# Procesador_Principal.net
KiCad netlist of a schematic drawn in Altium Designer
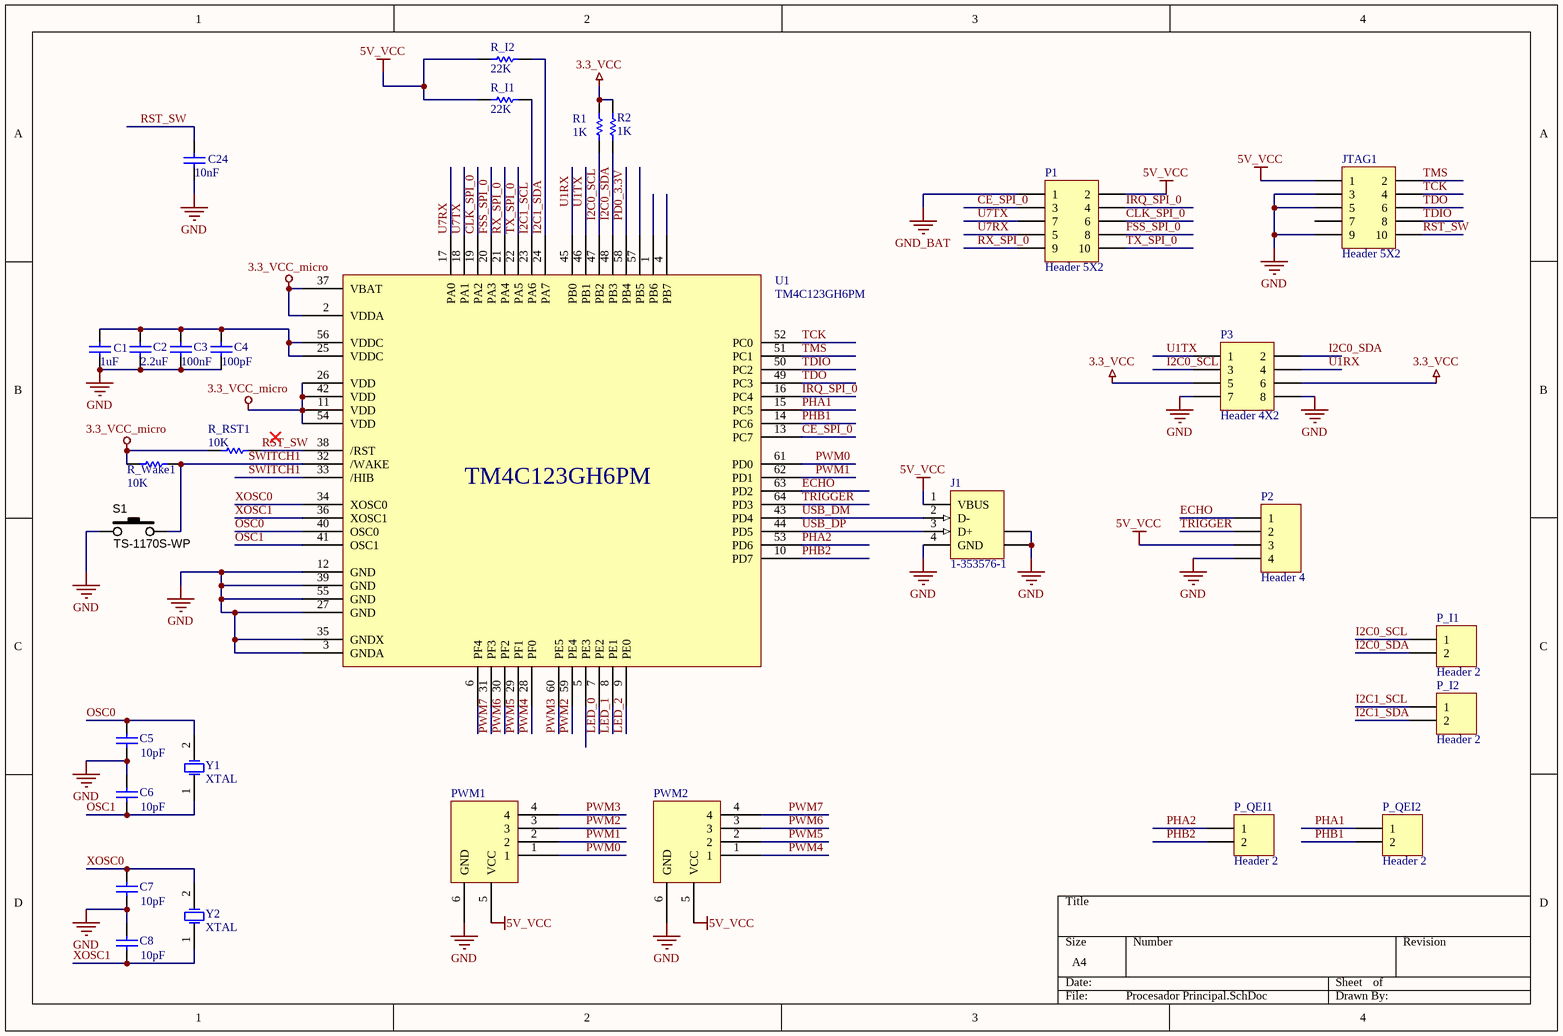
[diagram p0: Procesador Principal.SchDoc]

(export (version "E")
  (design (tool "Eeschema 10.0.6"))
  (components
    (comp (ref "C1")
      (value "1uF")
      (footprint "6-0805_L")
      (description "Capacitor")
      (fields (field (name "Comment") "Cap") (field (name "PUBLISHER") "Altium Limited"))
      (libsource (lib "Miscellaneous Devices") (part "Cap"))
    )
    (comp (ref "C2")
      (value "2.2uF")
      (footprint "6-0805_L")
      (description "Capacitor")
      (fields (field (name "Comment") "Cap") (field (name "PUBLISHER") "Altium Limited"))
      (libsource (lib "Miscellaneous Devices") (part "Cap"))
    )
    (comp (ref "C3")
      (value "100nF")
      (footprint "6-0805_L")
      (description "Capacitor")
      (fields (field (name "Comment") "Cap") (field (name "PUBLISHER") "Altium Limited"))
      (libsource (lib "Miscellaneous Devices") (part "Cap"))
    )
    (comp (ref "C4")
      (value "100pF")
      (footprint "6-0805_L")
      (description "Capacitor")
      (fields (field (name "Comment") "Cap") (field (name "PUBLISHER") "Altium Limited"))
      (libsource (lib "Miscellaneous Devices") (part "Cap"))
    )
    (comp (ref "C5")
      (value "10pF")
      (footprint "Miscellaneous Devices:C0805")
      (description "Capacitor")
      (fields (field (name "Comment") "Cap") (field (name "PUBLISHER") "Altium Limited"))
      (libsource (lib "Miscellaneous Devices") (part "Cap"))
    )
    (comp (ref "C6")
      (value "10pF")
      (footprint "Miscellaneous Devices:C0805")
      (description "Capacitor")
      (fields (field (name "Comment") "Cap") (field (name "PUBLISHER") "Altium Limited"))
      (libsource (lib "Miscellaneous Devices") (part "Cap"))
    )
    (comp (ref "C7")
      (value "10pF")
      (footprint "Miscellaneous Devices:C0805")
      (description "Capacitor")
      (fields (field (name "Comment") "Cap") (field (name "PUBLISHER") "Altium Limited"))
      (libsource (lib "Miscellaneous Devices") (part "Cap"))
    )
    (comp (ref "C8")
      (value "10pF")
      (footprint "Miscellaneous Devices:C0805")
      (description "Capacitor")
      (fields (field (name "Comment") "Cap") (field (name "PUBLISHER") "Altium Limited"))
      (libsource (lib "Miscellaneous Devices") (part "Cap"))
    )
    (comp (ref "C24")
      (value "10nF")
      (footprint "6-0805_L")
      (description "Capacitor")
      (fields (field (name "Comment") "Cap") (field (name "PUBLISHER") "Altium Limited"))
      (libsource (lib "Miscellaneous Devices") (part "Cap"))
    )
    (comp (ref "J1")
      (value "1-353576-1")
      (footprint "Micro USB")
      (description "USB 1.1, Right Angle, SMT, A Type, Receptacle, 4 Position, White")
      (fields (field (name "PUBLISHER") "Altium Limited"))
      (libsource (lib "AMP Serial Bus USB") (part "1-353576-1"))
    )
    (comp (ref "JTAG1")
      (value "Header 5X2")
      (footprint "HDR2X5")
      (description "Header, 5-Pin, Dual row")
      (fields (field (name "PUBLISHER") "Altium Limited"))
      (libsource (lib "") (part "Header 5X2_1"))
    )
    (comp (ref "P1")
      (value "Header 5X2")
      (footprint "SMD_HEADER 5x2")
      (description "Header, 5-Pin, Dual row")
      (fields (field (name "PUBLISHER") "Altium Limited"))
      (libsource (lib "Miscellaneous Connectors") (part "Header 5X2"))
    )
    (comp (ref "P2")
      (value "Header 4")
      (footprint "HDR1X4")
      (description "Header, 4-Pin")
      (fields (field (name "PUBLISHER") "Altium Limited"))
      (libsource (lib "Miscellaneous Connectors") (part "Header 4"))
    )
    (comp (ref "P3")
      (value "Header 4X2")
      (footprint "SMD_HEADER 4x2")
      (description "Header, 4-Pin, Dual row")
      (fields (field (name "PUBLISHER") "Altium Limited"))
      (libsource (lib "Miscellaneous Connectors") (part "Header 4X2"))
    )
    (comp (ref "PWM1")
      (value "Header 4 x 3")
      (footprint "Header_4x3_mirror")
      (libsource (lib "Conector") (part "Header 4 x 3"))
    )
    (comp (ref "PWM2")
      (value "Header 4 x 3")
      (footprint "Header_4x3")
      (libsource (lib "Conector") (part "Header 4 x 3"))
    )
    (comp (ref "P_I1")
      (value "Header 2")
      (footprint "HDR1X2")
      (description "Header, 2-Pin")
      (fields (field (name "PUBLISHER") "Altium Limited"))
      (libsource (lib "Miscellaneous Connectors") (part "Header 2"))
    )
    (comp (ref "P_I2")
      (value "Header 2")
      (footprint "HDR1X2")
      (description "Header, 2-Pin")
      (fields (field (name "PUBLISHER") "Altium Limited"))
      (libsource (lib "Miscellaneous Connectors") (part "Header 2"))
    )
    (comp (ref "P_QEI1")
      (value "Header 2")
      (footprint "HDR1X2")
      (description "Header, 2-Pin")
      (fields (field (name "PUBLISHER") "Altium Limited"))
      (libsource (lib "Miscellaneous Connectors") (part "Header 2"))
    )
    (comp (ref "P_QEI2")
      (value "Header 2")
      (footprint "HDR1X2")
      (description "Header, 2-Pin")
      (fields (field (name "PUBLISHER") "Altium Limited"))
      (libsource (lib "Miscellaneous Connectors") (part "Header 2"))
    )
    (comp (ref "R1")
      (value "1K")
      (footprint "C0805")
      (description "Resistor")
      (fields (field (name "Comment") "Res1") (field (name "PUBLISHER") "Altium Limited"))
      (libsource (lib "Miscellaneous Devices") (part "Res1"))
    )
    (comp (ref "R2")
      (value "1K")
      (footprint "6-0805_L")
      (description "Resistor")
      (fields (field (name "Comment") "Res1") (field (name "PUBLISHER") "Altium Limited"))
      (libsource (lib "Miscellaneous Devices") (part "Res1"))
    )
    (comp (ref "R_I1")
      (value "22K")
      (footprint "C1206")
      (description "Resistor")
      (fields (field (name "Comment") "Res1") (field (name "PUBLISHER") "Altium Limited"))
      (libsource (lib "Miscellaneous Devices") (part "Res1"))
    )
    (comp (ref "R_I2")
      (value "22K")
      (footprint "C1206")
      (description "Resistor")
      (fields (field (name "Comment") "Res1") (field (name "PUBLISHER") "Altium Limited"))
      (libsource (lib "Miscellaneous Devices") (part "Res1"))
    )
    (comp (ref "R_RST1")
      (value "10K")
      (footprint "C1206")
      (description "Resistor")
      (fields (field (name "Comment") "Res1") (field (name "PUBLISHER") "Altium Limited"))
      (libsource (lib "Miscellaneous Devices") (part "Res1"))
    )
    (comp (ref "R_Wake1")
      (value "10K")
      (footprint "C0805")
      (description "Resistor")
      (fields (field (name "Comment") "Res1") (field (name "PUBLISHER") "Altium Limited"))
      (libsource (lib "Miscellaneous Devices") (part "Res1"))
    )
    (comp (ref "S1")
      (value "TS-1170S-WP")
      (footprint "TS-1170S")
      (description "Switch SMD Tact 7.0mm Stem")
      (libsource (lib "PBL - Switches") (part "SW_SMD_PB_7.0mm"))
    )
    (comp (ref "U1")
      (value "TM4C123GH6PM")
      (footprint "QFP_Shrink_Sq_50P_Side_L:SQFP50P1200X1200-64L")
      (libsource (lib "ARM") (part "TM4C123GH6PM"))
    )
    (comp (ref "Y1")
      (value "XTAL")
      (footprint "CFPX-5")
      (description "Crystal Oscillator")
      (fields (field (name "PUBLISHER") "Altium Limited"))
      (libsource (lib "Miscellaneous Devices") (part "XTAL"))
    )
    (comp (ref "Y2")
      (value "XTAL")
      (footprint "Crystal Oscillator:BCY-W2/D2.1")
      (description "Crystal Oscillator")
      (fields (field (name "PUBLISHER") "Altium Limited"))
      (libsource (lib "Miscellaneous Devices") (part "XTAL"))
    )
  )
  (nets
    (net (code "1") (name "/CE_SPI_0") (class "Default")
      (node (ref "P1") (pin "3") (pinfunction "3_3") (pintype "passive"))
      (node (ref "U1") (pin "13") (pinfunction "PC7_13") (pintype "passive"))
    )
    (net (code "2") (name "/CLK_SPI_0") (class "Default")
      (node (ref "P1") (pin "6") (pinfunction "6_6") (pintype "passive"))
      (node (ref "U1") (pin "19") (pinfunction "PA2_19") (pintype "passive"))
    )
    (net (code "3") (name "/ECHO") (class "Default")
      (node (ref "P2") (pin "1") (pinfunction "1_1") (pintype "passive"))
      (node (ref "U1") (pin "63") (pinfunction "PD2_63") (pintype "passive"))
    )
    (net (code "4") (name "/FSS_SPI_0") (class "Default")
      (node (ref "P1") (pin "8") (pinfunction "8_8") (pintype "passive"))
      (node (ref "U1") (pin "20") (pinfunction "PA3_20") (pintype "passive"))
    )
    (net (code "5") (name "/I2C0_SCL") (class "Default")
      (node (ref "P3") (pin "3") (pinfunction "3_3") (pintype "passive"))
      (node (ref "P_I1") (pin "1") (pinfunction "1_1") (pintype "passive"))
      (node (ref "R1") (pin "2") (pinfunction "2_2") (pintype "passive"))
      (node (ref "U1") (pin "47") (pinfunction "PB2_47") (pintype "passive"))
    )
    (net (code "6") (name "/I2C0_SDA") (class "Default")
      (node (ref "P3") (pin "2") (pinfunction "2_2") (pintype "passive"))
      (node (ref "P_I1") (pin "2") (pinfunction "2_2") (pintype "passive"))
      (node (ref "R2") (pin "1") (pinfunction "1_1") (pintype "passive"))
      (node (ref "U1") (pin "48") (pinfunction "PB3_48") (pintype "passive"))
    )
    (net (code "7") (name "/I2C1_SCL") (class "Default")
      (node (ref "P_I2") (pin "1") (pinfunction "1_1") (pintype "passive"))
      (node (ref "R_I1") (pin "1") (pinfunction "1_1") (pintype "passive"))
      (node (ref "U1") (pin "23") (pinfunction "PA6_23") (pintype "passive"))
    )
    (net (code "8") (name "/I2C1_SDA") (class "Default")
      (node (ref "P_I2") (pin "2") (pinfunction "2_2") (pintype "passive"))
      (node (ref "R_I2") (pin "1") (pinfunction "1_1") (pintype "passive"))
      (node (ref "U1") (pin "24") (pinfunction "PA7_24") (pintype "passive"))
    )
    (net (code "9") (name "/IRQ_SPI_0") (class "Default")
      (node (ref "P1") (pin "4") (pinfunction "4_4") (pintype "passive"))
      (node (ref "U1") (pin "16") (pinfunction "PC4_16") (pintype "passive"))
    )
    (net (code "10") (name "/LED_0") (class "Default")
      (node (ref "U1") (pin "7") (pinfunction "PE2_7") (pintype "passive"))
    )
    (net (code "11") (name "/LED_1") (class "Default")
      (node (ref "U1") (pin "8") (pinfunction "PE1_8") (pintype "passive"))
    )
    (net (code "12") (name "/LED_2") (class "Default")
      (node (ref "U1") (pin "9") (pinfunction "PE0_9") (pintype "passive"))
    )
    (net (code "13") (name "/OSC0") (class "Default")
      (node (ref "C5") (pin "2") (pinfunction "2_2") (pintype "passive"))
      (node (ref "U1") (pin "40") (pinfunction "OSC0_40") (pintype "passive"))
      (node (ref "Y1") (pin "2") (pinfunction "OSC2_2") (pintype "passive"))
    )
    (net (code "14") (name "/OSC1") (class "Default")
      (node (ref "C6") (pin "1") (pinfunction "1_1") (pintype "passive"))
      (node (ref "U1") (pin "41") (pinfunction "OSC1_41") (pintype "passive"))
      (node (ref "Y1") (pin "1") (pinfunction "OSC1_1") (pintype "passive"))
    )
    (net (code "15") (name "/PD0_3.3V") (class "Default")
      (node (ref "U1") (pin "58") (pinfunction "PB4_58") (pintype "passive"))
    )
    (net (code "16") (name "/PHA1") (class "Default")
      (node (ref "P_QEI2") (pin "1") (pinfunction "1_1") (pintype "passive"))
      (node (ref "U1") (pin "15") (pinfunction "PC5_15") (pintype "passive"))
    )
    (net (code "17") (name "/PHA2") (class "Default")
      (node (ref "P_QEI1") (pin "1") (pinfunction "1_1") (pintype "passive"))
      (node (ref "U1") (pin "53") (pinfunction "PD6_53") (pintype "passive"))
    )
    (net (code "18") (name "/PHB1") (class "Default")
      (node (ref "P_QEI2") (pin "2") (pinfunction "2_2") (pintype "passive"))
      (node (ref "U1") (pin "14") (pinfunction "PC6_14") (pintype "passive"))
    )
    (net (code "19") (name "/PHB2") (class "Default")
      (node (ref "P_QEI1") (pin "2") (pinfunction "2_2") (pintype "passive"))
      (node (ref "U1") (pin "10") (pinfunction "PD7_10") (pintype "passive"))
    )
    (net (code "20") (name "/PWM0") (class "Default")
      (node (ref "PWM1") (pin "1") (pinfunction "1_1") (pintype "passive"))
      (node (ref "U1") (pin "61") (pinfunction "PD0_61") (pintype "passive"))
    )
    (net (code "21") (name "/PWM1") (class "Default")
      (node (ref "PWM1") (pin "2") (pinfunction "2_2") (pintype "passive"))
      (node (ref "U1") (pin "62") (pinfunction "PD1_62") (pintype "passive"))
    )
    (net (code "22") (name "/PWM2") (class "Default")
      (node (ref "PWM1") (pin "3") (pinfunction "3_3") (pintype "passive"))
      (node (ref "U1") (pin "59") (pinfunction "PE4_59") (pintype "passive"))
    )
    (net (code "23") (name "/PWM3") (class "Default")
      (node (ref "PWM1") (pin "4") (pinfunction "4_4") (pintype "passive"))
      (node (ref "U1") (pin "60") (pinfunction "PE5_60") (pintype "passive"))
    )
    (net (code "24") (name "/PWM4") (class "Default")
      (node (ref "PWM2") (pin "1") (pinfunction "1_1") (pintype "passive"))
      (node (ref "U1") (pin "28") (pinfunction "PF0_28") (pintype "passive"))
    )
    (net (code "25") (name "/PWM5") (class "Default")
      (node (ref "PWM2") (pin "2") (pinfunction "2_2") (pintype "passive"))
      (node (ref "U1") (pin "29") (pinfunction "PF1_29") (pintype "passive"))
    )
    (net (code "26") (name "/PWM6") (class "Default")
      (node (ref "PWM2") (pin "3") (pinfunction "3_3") (pintype "passive"))
      (node (ref "U1") (pin "30") (pinfunction "PF2_30") (pintype "passive"))
    )
    (net (code "27") (name "/PWM7") (class "Default")
      (node (ref "PWM2") (pin "4") (pinfunction "4_4") (pintype "passive"))
      (node (ref "U1") (pin "31") (pinfunction "PF3_31") (pintype "passive"))
    )
    (net (code "28") (name "/RST_SW") (class "Default")
      (node (ref "C24") (pin "2") (pinfunction "2_2") (pintype "passive"))
      (node (ref "JTAG1") (pin "10") (pinfunction "10_10") (pintype "passive"))
      (node (ref "R_RST1") (pin "2") (pinfunction "2_2") (pintype "passive"))
      (node (ref "U1") (pin "38") (pinfunction "/RST_38") (pintype "passive"))
    )
    (net (code "29") (name "/RX_SPI_0") (class "Default")
      (node (ref "P1") (pin "9") (pinfunction "9_9") (pintype "passive"))
      (node (ref "U1") (pin "21") (pinfunction "PA4_21") (pintype "passive"))
    )
    (net (code "30") (name "/SWITCH1") (class "Default")
      (node (ref "R_Wake1") (pin "2") (pinfunction "2_2") (pintype "passive"))
      (node (ref "S1") (pin "2") (pintype "passive"))
      (node (ref "U1") (pin "32") (pinfunction "/WAKE_32") (pintype "passive"))
      (node (ref "U1") (pin "33") (pinfunction "/HIB_33") (pintype "passive"))
    )
    (net (code "31") (name "/TCK") (class "Default")
      (node (ref "JTAG1") (pin "4") (pinfunction "4_4") (pintype "passive"))
      (node (ref "U1") (pin "52") (pinfunction "PC0_52") (pintype "passive"))
    )
    (net (code "32") (name "/TDIO") (class "Default")
      (node (ref "JTAG1") (pin "8") (pinfunction "8_8") (pintype "passive"))
      (node (ref "U1") (pin "50") (pinfunction "PC2_50") (pintype "passive"))
    )
    (net (code "33") (name "/TDO") (class "Default")
      (node (ref "JTAG1") (pin "6") (pinfunction "6_6") (pintype "passive"))
      (node (ref "U1") (pin "49") (pinfunction "PC3_49") (pintype "passive"))
    )
    (net (code "34") (name "/TMS") (class "Default")
      (node (ref "JTAG1") (pin "2") (pinfunction "2_2") (pintype "passive"))
      (node (ref "U1") (pin "51") (pinfunction "PC1_51") (pintype "passive"))
    )
    (net (code "35") (name "/TRIGGER") (class "Default")
      (node (ref "P2") (pin "2") (pinfunction "2_2") (pintype "passive"))
      (node (ref "U1") (pin "64") (pinfunction "PD3_64") (pintype "passive"))
    )
    (net (code "36") (name "/TX_SPI_0") (class "Default")
      (node (ref "P1") (pin "10") (pinfunction "10_10") (pintype "passive"))
      (node (ref "U1") (pin "22") (pinfunction "PA5_22") (pintype "passive"))
    )
    (net (code "37") (name "/U1RX") (class "Default")
      (node (ref "P3") (pin "4") (pinfunction "4_4") (pintype "passive"))
      (node (ref "U1") (pin "45") (pinfunction "PB0_45") (pintype "passive"))
    )
    (net (code "38") (name "/U1TX") (class "Default")
      (node (ref "P3") (pin "1") (pinfunction "1_1") (pintype "passive"))
      (node (ref "U1") (pin "46") (pinfunction "PB1_46") (pintype "passive"))
    )
    (net (code "39") (name "/U7RX") (class "Default")
      (node (ref "P1") (pin "5") (pinfunction "5_5") (pintype "passive"))
      (node (ref "U1") (pin "17") (pinfunction "PA0_17") (pintype "passive"))
    )
    (net (code "40") (name "/U7TX") (class "Default")
      (node (ref "P1") (pin "7") (pinfunction "7_7") (pintype "passive"))
      (node (ref "U1") (pin "18") (pinfunction "PA1_18") (pintype "passive"))
    )
    (net (code "41") (name "/USB_DM") (class "Default")
      (node (ref "J1") (pin "2") (pinfunction "D-_2") (pintype "input"))
      (node (ref "U1") (pin "43") (pinfunction "PD4_43") (pintype "passive"))
    )
    (net (code "42") (name "/USB_DP") (class "Default")
      (node (ref "J1") (pin "3") (pinfunction "D+_3") (pintype "input"))
      (node (ref "U1") (pin "44") (pinfunction "PD5_44") (pintype "passive"))
    )
    (net (code "43") (name "/XOSC0") (class "Default")
      (node (ref "C7") (pin "2") (pinfunction "2_2") (pintype "passive"))
      (node (ref "U1") (pin "34") (pinfunction "XOSC0_34") (pintype "passive"))
      (node (ref "Y2") (pin "2") (pinfunction "OSC2_2") (pintype "passive"))
    )
    (net (code "44") (name "/XOSC1") (class "Default")
      (node (ref "C8") (pin "1") (pinfunction "1_1") (pintype "passive"))
      (node (ref "U1") (pin "36") (pinfunction "XOSC1_36") (pintype "passive"))
      (node (ref "Y2") (pin "1") (pinfunction "OSC1_1") (pintype "passive"))
    )
    (net (code "45") (name "3.3_VCC") (class "Default")
      (node (ref "P3") (pin "5") (pinfunction "5_5") (pintype "passive"))
      (node (ref "P3") (pin "6") (pinfunction "6_6") (pintype "passive"))
      (node (ref "R1") (pin "1") (pinfunction "1_1") (pintype "passive"))
      (node (ref "R2") (pin "2") (pinfunction "2_2") (pintype "passive"))
    )
    (net (code "46") (name "3.3_VCC_micro") (class "Default")
      (node (ref "R_RST1") (pin "1") (pinfunction "1_1") (pintype "passive"))
      (node (ref "R_Wake1") (pin "1") (pinfunction "1_1") (pintype "passive"))
      (node (ref "U1") (pin "11") (pinfunction "VDD_11") (pintype "passive"))
      (node (ref "U1") (pin "2") (pinfunction "VDDA_2") (pintype "passive"))
      (node (ref "U1") (pin "26") (pinfunction "VDD_26") (pintype "passive"))
      (node (ref "U1") (pin "37") (pinfunction "VBAT_37") (pintype "passive"))
      (node (ref "U1") (pin "42") (pinfunction "VDD_42") (pintype "passive"))
      (node (ref "U1") (pin "54") (pinfunction "VDD_54") (pintype "passive"))
    )
    (net (code "47") (name "5V_VCC") (class "Default")
      (node (ref "J1") (pin "1") (pinfunction "VBUS_1") (pintype "power_in"))
      (node (ref "JTAG1") (pin "1") (pinfunction "1_1") (pintype "passive"))
      (node (ref "P1") (pin "2") (pinfunction "2_2") (pintype "passive"))
      (node (ref "P2") (pin "3") (pinfunction "3_3") (pintype "passive"))
      (node (ref "PWM1") (pin "5") (pinfunction "VCC_5") (pintype "passive"))
      (node (ref "PWM2") (pin "5") (pinfunction "VCC_5") (pintype "passive"))
      (node (ref "R_I1") (pin "2") (pinfunction "2_2") (pintype "passive"))
      (node (ref "R_I2") (pin "2") (pinfunction "2_2") (pintype "passive"))
    )
    (net (code "48") (name "GND") (class "Default")
      (node (ref "C1") (pin "1") (pinfunction "1_1") (pintype "passive"))
      (node (ref "C2") (pin "1") (pinfunction "1_1") (pintype "passive"))
      (node (ref "C24") (pin "1") (pinfunction "1_1") (pintype "passive"))
      (node (ref "C3") (pin "1") (pinfunction "1_1") (pintype "passive"))
      (node (ref "C4") (pin "1") (pinfunction "1_1") (pintype "passive"))
      (node (ref "C5") (pin "1") (pinfunction "1_1") (pintype "passive"))
      (node (ref "C6") (pin "2") (pinfunction "2_2") (pintype "passive"))
      (node (ref "C7") (pin "1") (pinfunction "1_1") (pintype "passive"))
      (node (ref "C8") (pin "2") (pinfunction "2_2") (pintype "passive"))
      (node (ref "J1") (pin "4") (pinfunction "GND_4") (pintype "power_in"))
      (node (ref "J1") (pin "5") (pinfunction "SHLD_5") (pintype "passive"))
      (node (ref "J1") (pin "6") (pinfunction "SHLD_6") (pintype "passive"))
      (node (ref "JTAG1") (pin "3") (pinfunction "3_3") (pintype "passive"))
      (node (ref "JTAG1") (pin "5") (pinfunction "5_5") (pintype "passive"))
      (node (ref "JTAG1") (pin "9") (pinfunction "9_9") (pintype "passive"))
      (node (ref "P2") (pin "4") (pinfunction "4_4") (pintype "passive"))
      (node (ref "P3") (pin "7") (pinfunction "7_7") (pintype "passive"))
      (node (ref "P3") (pin "8") (pinfunction "8_8") (pintype "passive"))
      (node (ref "PWM1") (pin "6") (pinfunction "GND_6") (pintype "passive"))
      (node (ref "PWM2") (pin "6") (pinfunction "GND_6") (pintype "passive"))
      (node (ref "S1") (pin "1") (pintype "passive"))
      (node (ref "U1") (pin "12") (pinfunction "GND_12") (pintype "passive"))
      (node (ref "U1") (pin "27") (pinfunction "GND_27") (pintype "passive"))
      (node (ref "U1") (pin "3") (pinfunction "GNDA_3") (pintype "passive"))
      (node (ref "U1") (pin "35") (pinfunction "GNDX_35") (pintype "passive"))
      (node (ref "U1") (pin "39") (pinfunction "GND_39") (pintype "passive"))
      (node (ref "U1") (pin "55") (pinfunction "GND_55") (pintype "passive"))
    )
    (net (code "49") (name "GND_BAT") (class "Default")
      (node (ref "P1") (pin "1") (pinfunction "1_1") (pintype "passive"))
    )
    (net (code "50") (name "Net-(C1-Pad2)") (class "Default")
      (node (ref "C1") (pin "2") (pinfunction "2_2") (pintype "passive"))
      (node (ref "C2") (pin "2") (pinfunction "2_2") (pintype "passive"))
      (node (ref "C3") (pin "2") (pinfunction "2_2") (pintype "passive"))
      (node (ref "C4") (pin "2") (pinfunction "2_2") (pintype "passive"))
      (node (ref "U1") (pin "25") (pinfunction "VDDC_25") (pintype "passive"))
      (node (ref "U1") (pin "56") (pinfunction "VDDC_56") (pintype "passive"))
    )
    (net (code "51") (name "unconnected-(JTAG1-Pad7)") (class "Default")
      (node (ref "JTAG1") (pin "7") (pinfunction "7_7") (pintype "passive"))
    )
    (net (code "52") (name "unconnected-(U1-PB5-Pad57)") (class "Default")
      (node (ref "U1") (pin "57") (pinfunction "PB5_57") (pintype "passive"))
    )
    (net (code "53") (name "unconnected-(U1-PB6-Pad1)") (class "Default")
      (node (ref "U1") (pin "1") (pinfunction "PB6_1") (pintype "passive"))
    )
    (net (code "54") (name "unconnected-(U1-PB7-Pad4)") (class "Default")
      (node (ref "U1") (pin "4") (pinfunction "PB7_4") (pintype "passive"))
    )
    (net (code "55") (name "unconnected-(U1-PE3-Pad5)") (class "Default")
      (node (ref "U1") (pin "5") (pinfunction "PE3_5") (pintype "passive"))
    )
    (net (code "56") (name "unconnected-(U1-PF4-Pad6)") (class "Default")
      (node (ref "U1") (pin "6") (pinfunction "PF4_6") (pintype "passive"))
    )
  )
)
